# LCD.net
KiCad netlist of a schematic drawn in Altium Designer
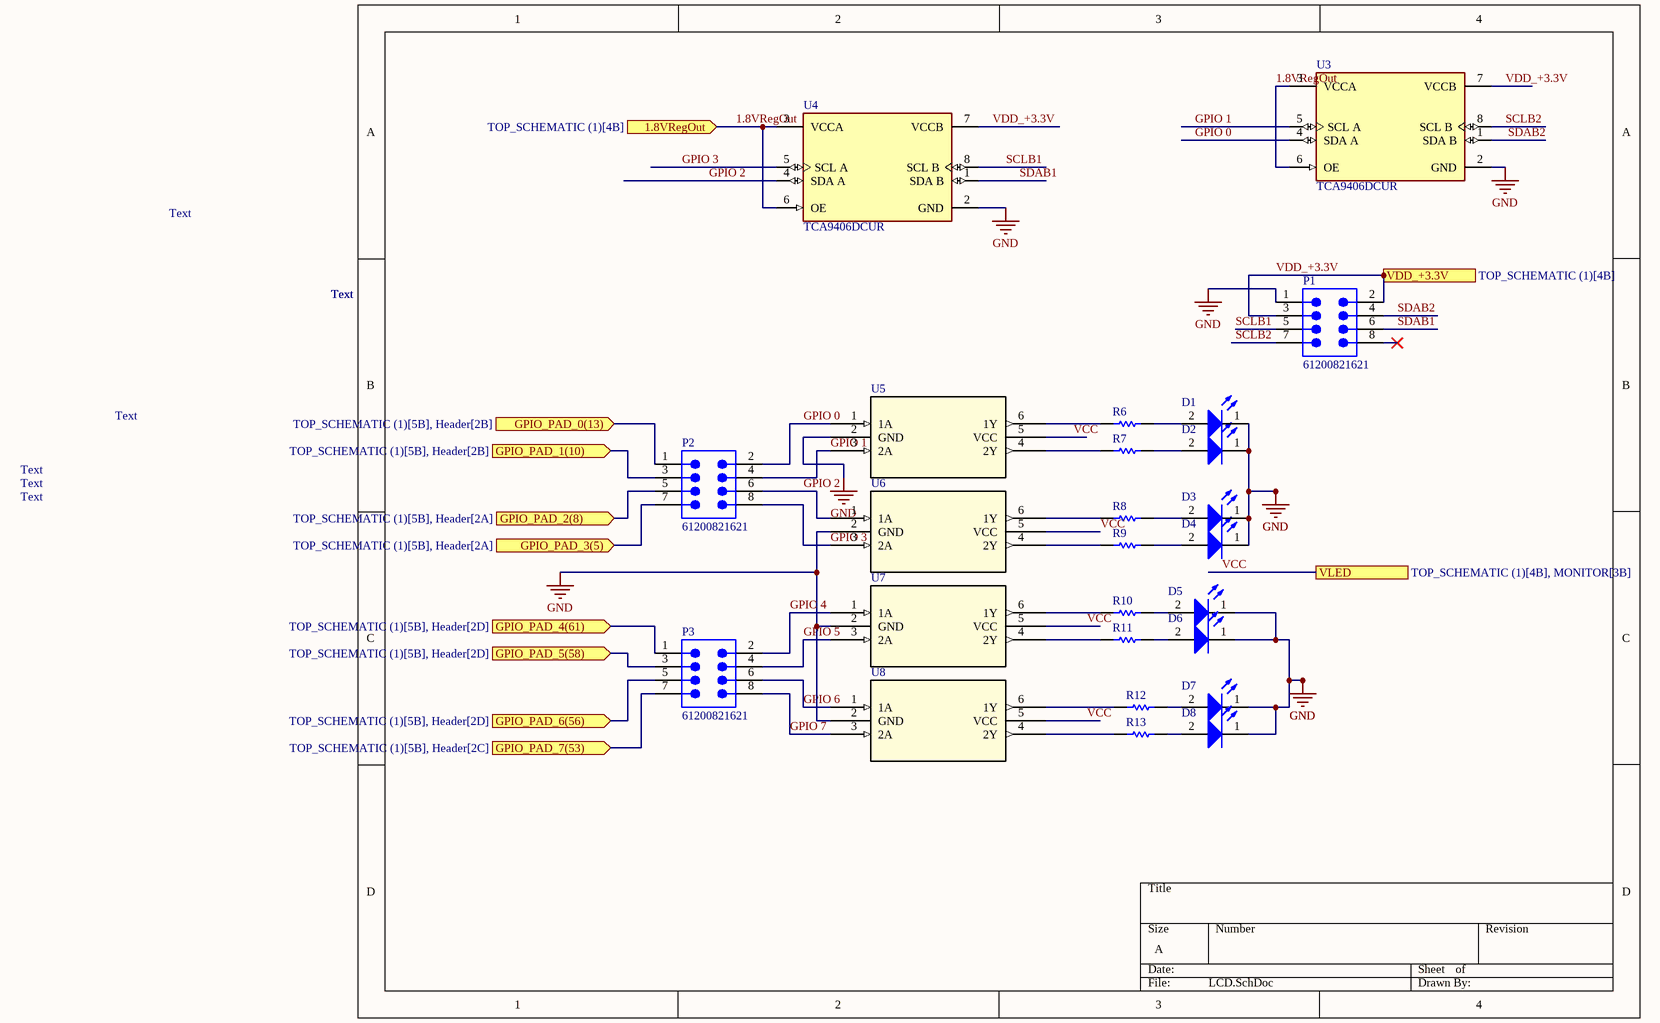
[diagram p0: LCD.SchDoc]

(export (version "E")
  (design (tool "Eeschema 10.0.6"))
  (components
    (comp (ref "D1")
      (value "150120BS75000")
      (footprint "WL-SMCW_1206_150120xx75000")
      (description "Wurth Elektronik LED, WL-SMCW, 3216 (1206), 470 nm, 3.2 x 1.6 x 0.68mm")
      (libsource (lib "Altium Content Vault") (part "LED_Blue_2A-1K"))
    )
    (comp (ref "D2")
      (value "150120BS75000")
      (footprint "WL-SMCW_1206_150120xx75000")
      (description "Wurth Elektronik LED, WL-SMCW, 3216 (1206), 470 nm, 3.2 x 1.6 x 0.68mm")
      (libsource (lib "Altium Content Vault") (part "LED_Blue_2A-1K"))
    )
    (comp (ref "D3")
      (value "150120BS75000")
      (footprint "WL-SMCW_1206_150120xx75000")
      (description "Wurth Elektronik LED, WL-SMCW, 3216 (1206), 470 nm, 3.2 x 1.6 x 0.68mm")
      (libsource (lib "Altium Content Vault") (part "LED_Blue_2A-1K"))
    )
    (comp (ref "D4")
      (value "150120BS75000")
      (footprint "WL-SMCW_1206_150120xx75000")
      (description "Wurth Elektronik LED, WL-SMCW, 3216 (1206), 470 nm, 3.2 x 1.6 x 0.68mm")
      (libsource (lib "Altium Content Vault") (part "LED_Blue_2A-1K"))
    )
    (comp (ref "D5")
      (value "150120BS75000")
      (footprint "WL-SMCW_1206_150120xx75000")
      (description "Wurth Elektronik LED, WL-SMCW, 3216 (1206), 470 nm, 3.2 x 1.6 x 0.68mm")
      (libsource (lib "Altium Content Vault") (part "LED_Blue_2A-1K"))
    )
    (comp (ref "D6")
      (value "150120BS75000")
      (footprint "WL-SMCW_1206_150120xx75000")
      (description "Wurth Elektronik LED, WL-SMCW, 3216 (1206), 470 nm, 3.2 x 1.6 x 0.68mm")
      (libsource (lib "Altium Content Vault") (part "LED_Blue_2A-1K"))
    )
    (comp (ref "D7")
      (value "150120BS75000")
      (footprint "WL-SMCW_1206_150120xx75000")
      (description "Wurth Elektronik LED, WL-SMCW, 3216 (1206), 470 nm, 3.2 x 1.6 x 0.68mm")
      (libsource (lib "Altium Content Vault") (part "LED_Blue_2A-1K"))
    )
    (comp (ref "D8")
      (value "150120BS75000")
      (footprint "WL-SMCW_1206_150120xx75000")
      (description "Wurth Elektronik LED, WL-SMCW, 3216 (1206), 470 nm, 3.2 x 1.6 x 0.68mm")
      (libsource (lib "Altium Content Vault") (part "LED_Blue_2A-1K"))
    )
    (comp (ref "P1")
      (value "61200821621")
      (footprint "61200821621")
      (description "Wr-bhd; 2.54MM Pitch 8 Way 2 Row Shrouded Straight Pcb Header, Surface Mount")
      (libsource (lib "Altium Content Vault") (part "Header_Male_2R_08P"))
    )
    (comp (ref "P2")
      (value "61200821621")
      (footprint "61200821621")
      (description "Wr-bhd; 2.54MM Pitch 8 Way 2 Row Shrouded Straight Pcb Header, Surface Mount")
      (libsource (lib "Altium Content Vault") (part "Header_Male_2R_08P"))
    )
    (comp (ref "P3")
      (value "61200821621")
      (footprint "61200821621")
      (description "Wr-bhd; 2.54MM Pitch 8 Way 2 Row Shrouded Straight Pcb Header, Surface Mount")
      (libsource (lib "Altium Content Vault") (part "Header_Male_2R_08P"))
    )
    (comp (ref "R6")
      (value "RC1206FR-10750RL")
      (footprint "RESC3116X65X40LL10T20")
      (fields (field (name "MANUFACTURER") "Yageo"))
      (libsource (lib "Altium Content Vault") (part "RES"))
    )
    (comp (ref "R7")
      (value "RC1206FR-10750RL")
      (footprint "RESC3116X65X40LL10T20")
      (fields (field (name "MANUFACTURER") "Yageo"))
      (libsource (lib "Altium Content Vault") (part "RES"))
    )
    (comp (ref "R8")
      (value "RC1206FR-10750RL")
      (footprint "RESC3116X65X40LL10T20")
      (fields (field (name "MANUFACTURER") "Yageo"))
      (libsource (lib "Altium Content Vault") (part "RES"))
    )
    (comp (ref "R9")
      (value "RC1206FR-10750RL")
      (footprint "RESC3116X65X40LL10T20")
      (fields (field (name "MANUFACTURER") "Yageo"))
      (libsource (lib "Altium Content Vault") (part "RES"))
    )
    (comp (ref "R10")
      (value "RC1206FR-10750RL")
      (footprint "RESC3116X65X40LL10T20")
      (fields (field (name "MANUFACTURER") "Yageo"))
      (libsource (lib "Altium Content Vault") (part "RES"))
    )
    (comp (ref "R11")
      (value "RC1206FR-10750RL")
      (footprint "RESC3116X65X40LL10T20")
      (fields (field (name "MANUFACTURER") "Yageo"))
      (libsource (lib "Altium Content Vault") (part "RES"))
    )
    (comp (ref "R12")
      (value "RC1206FR-10750RL")
      (footprint "RESC3116X65X40LL10T20")
      (fields (field (name "MANUFACTURER") "Yageo"))
      (libsource (lib "Altium Content Vault") (part "RES"))
    )
    (comp (ref "R13")
      (value "RC1206FR-10750RL")
      (footprint "RESC3116X65X40LL10T20")
      (fields (field (name "MANUFACTURER") "Yageo"))
      (libsource (lib "Altium Content Vault") (part "RES"))
    )
    (comp (ref "U3")
      (value "TCA9406DCUR")
      (footprint "FP-DCU0008A-IPC_B")
      (description "IC TRNSLTR BIDIRECTIONAL US8")
      (libsource (lib "Altium Content Vault") (part "2e2e7ab415e70eec0fdfb76e593e2e7"))
    )
    (comp (ref "U4")
      (value "TCA9406DCUR")
      (footprint "FP-DCU0008A-IPC_B")
      (description "IC TRNSLTR BIDIRECTIONAL US8")
      (libsource (lib "Altium Content Vault") (part "2e2e7ab415e70eec0fdfb76e593e2e7"))
    )
    (comp (ref "U5")
      (value "74LVC2G17GV,125")
      (footprint "SC-74;TSOP6_NEX")
      (description "Description")
      (fields (field (name "COPYRIGHT") "Copyright (C) 2026 Ultra Librarian. All rights reserved."))
      (libsource (lib "74LVC2G17GV,125") (part "74LVC2G17GV,125"))
    )
    (comp (ref "U6")
      (value "74LVC2G17GV,125")
      (footprint "SC-74;TSOP6_NEX")
      (description "Description")
      (fields (field (name "COPYRIGHT") "Copyright (C) 2026 Ultra Librarian. All rights reserved."))
      (libsource (lib "74LVC2G17GV,125") (part "74LVC2G17GV,125"))
    )
    (comp (ref "U7")
      (value "74LVC2G17GV,125")
      (footprint "SC-74;TSOP6_NEX")
      (description "Description")
      (fields (field (name "COPYRIGHT") "Copyright (C) 2026 Ultra Librarian. All rights reserved."))
      (libsource (lib "74LVC2G17GV,125") (part "74LVC2G17GV,125"))
    )
    (comp (ref "U8")
      (value "74LVC2G17GV,125")
      (footprint "SC-74;TSOP6_NEX")
      (description "Description")
      (fields (field (name "COPYRIGHT") "Copyright (C) 2026 Ultra Librarian. All rights reserved."))
      (libsource (lib "74LVC2G17GV,125") (part "74LVC2G17GV,125"))
    )
  )
  (nets
    (net (code "1") (name "/1.8VRegOut") (class "Default")
      (node (ref "U3") (pin "3") (pinfunction "VCCA_3") (pintype "power_in"))
      (node (ref "U3") (pin "6") (pinfunction "OE_6") (pintype "input"))
      (node (ref "U4") (pin "3") (pinfunction "VCCA_3") (pintype "power_in"))
      (node (ref "U4") (pin "6") (pinfunction "OE_6") (pintype "input"))
    )
    (net (code "2") (name "/GPIO 0") (class "Default")
      (node (ref "P2") (pin "2") (pinfunction "2_2") (pintype "passive"))
      (node (ref "U3") (pin "4") (pinfunction "SDA_A_4") (pintype "bidirectional"))
      (node (ref "U5") (pin "1") (pinfunction "1A_1") (pintype "input"))
    )
    (net (code "3") (name "/GPIO 1") (class "Default")
      (node (ref "P2") (pin "4") (pinfunction "4_4") (pintype "passive"))
      (node (ref "U3") (pin "5") (pinfunction "SCL_A_5") (pintype "bidirectional"))
      (node (ref "U5") (pin "3") (pinfunction "2A_3") (pintype "input"))
    )
    (net (code "4") (name "/GPIO 2") (class "Default")
      (node (ref "P2") (pin "6") (pinfunction "6_6") (pintype "passive"))
      (node (ref "U4") (pin "4") (pinfunction "SDA_A_4") (pintype "bidirectional"))
      (node (ref "U6") (pin "1") (pinfunction "1A_1") (pintype "input"))
    )
    (net (code "5") (name "/GPIO 3") (class "Default")
      (node (ref "P2") (pin "8") (pinfunction "8_8") (pintype "passive"))
      (node (ref "U4") (pin "5") (pinfunction "SCL_A_5") (pintype "bidirectional"))
      (node (ref "U6") (pin "3") (pinfunction "2A_3") (pintype "input"))
    )
    (net (code "6") (name "/GPIO 4") (class "Default")
      (node (ref "P3") (pin "2") (pinfunction "2_2") (pintype "passive"))
      (node (ref "U7") (pin "1") (pinfunction "1A_1") (pintype "input"))
    )
    (net (code "7") (name "/GPIO 5") (class "Default")
      (node (ref "P3") (pin "4") (pinfunction "4_4") (pintype "passive"))
      (node (ref "U7") (pin "3") (pinfunction "2A_3") (pintype "input"))
    )
    (net (code "8") (name "/GPIO 6") (class "Default")
      (node (ref "P3") (pin "6") (pinfunction "6_6") (pintype "passive"))
      (node (ref "U8") (pin "1") (pinfunction "1A_1") (pintype "input"))
    )
    (net (code "9") (name "/GPIO 7") (class "Default")
      (node (ref "P3") (pin "8") (pinfunction "8_8") (pintype "passive"))
      (node (ref "U8") (pin "3") (pinfunction "2A_3") (pintype "input"))
    )
    (net (code "10") (name "/GPIO_PAD_0(13)") (class "Default")
      (node (ref "P2") (pin "1") (pinfunction "1_1") (pintype "passive"))
    )
    (net (code "11") (name "/GPIO_PAD_1(10)") (class "Default")
      (node (ref "P2") (pin "3") (pinfunction "3_3") (pintype "passive"))
    )
    (net (code "12") (name "/GPIO_PAD_2(8)") (class "Default")
      (node (ref "P2") (pin "5") (pinfunction "5_5") (pintype "passive"))
    )
    (net (code "13") (name "/GPIO_PAD_3(5)") (class "Default")
      (node (ref "P2") (pin "7") (pinfunction "7_7") (pintype "passive"))
    )
    (net (code "14") (name "/GPIO_PAD_4(61)") (class "Default")
      (node (ref "P3") (pin "1") (pinfunction "1_1") (pintype "passive"))
    )
    (net (code "15") (name "/GPIO_PAD_5(58)") (class "Default")
      (node (ref "P3") (pin "3") (pinfunction "3_3") (pintype "passive"))
    )
    (net (code "16") (name "/GPIO_PAD_6(56)") (class "Default")
      (node (ref "P3") (pin "5") (pinfunction "5_5") (pintype "passive"))
    )
    (net (code "17") (name "/GPIO_PAD_7(53)") (class "Default")
      (node (ref "P3") (pin "7") (pinfunction "7_7") (pintype "passive"))
    )
    (net (code "18") (name "/SCLB1") (class "Default")
      (node (ref "P1") (pin "5") (pinfunction "5_5") (pintype "passive"))
      (node (ref "U4") (pin "8") (pinfunction "SCL_B_8") (pintype "bidirectional"))
    )
    (net (code "19") (name "/SCLB2") (class "Default")
      (node (ref "P1") (pin "7") (pinfunction "7_7") (pintype "passive"))
      (node (ref "U3") (pin "8") (pinfunction "SCL_B_8") (pintype "bidirectional"))
    )
    (net (code "20") (name "/SDAB1") (class "Default")
      (node (ref "P1") (pin "6") (pinfunction "6_6") (pintype "passive"))
      (node (ref "U4") (pin "1") (pinfunction "SDA_B_1") (pintype "bidirectional"))
    )
    (net (code "21") (name "/SDAB2") (class "Default")
      (node (ref "P1") (pin "4") (pinfunction "4_4") (pintype "passive"))
      (node (ref "U3") (pin "1") (pinfunction "SDA_B_1") (pintype "bidirectional"))
    )
    (net (code "22") (name "/VCC") (class "Default")
      (node (ref "U5") (pin "5") (pinfunction "VCC_5") (pintype "power_in"))
      (node (ref "U6") (pin "5") (pinfunction "VCC_5") (pintype "power_in"))
      (node (ref "U7") (pin "5") (pinfunction "VCC_5") (pintype "power_in"))
      (node (ref "U8") (pin "5") (pinfunction "VCC_5") (pintype "power_in"))
    )
    (net (code "23") (name "/VDD_+3.3V") (class "Default")
      (node (ref "P1") (pin "2") (pinfunction "2_2") (pintype "passive"))
      (node (ref "P1") (pin "3") (pinfunction "3_3") (pintype "passive"))
      (node (ref "U3") (pin "7") (pinfunction "VCCB_7") (pintype "power_in"))
      (node (ref "U4") (pin "7") (pinfunction "VCCB_7") (pintype "power_in"))
    )
    (net (code "24") (name "GND") (class "Default")
      (node (ref "D1") (pin "1") (pinfunction "K_1") (pintype "passive"))
      (node (ref "D2") (pin "1") (pinfunction "K_1") (pintype "passive"))
      (node (ref "D3") (pin "1") (pinfunction "K_1") (pintype "passive"))
      (node (ref "D4") (pin "1") (pinfunction "K_1") (pintype "passive"))
      (node (ref "D5") (pin "1") (pinfunction "K_1") (pintype "passive"))
      (node (ref "D6") (pin "1") (pinfunction "K_1") (pintype "passive"))
      (node (ref "D7") (pin "1") (pinfunction "K_1") (pintype "passive"))
      (node (ref "D8") (pin "1") (pinfunction "K_1") (pintype "passive"))
      (node (ref "P1") (pin "1") (pinfunction "1_1") (pintype "passive"))
      (node (ref "U3") (pin "2") (pinfunction "GND_2") (pintype "power_in"))
      (node (ref "U4") (pin "2") (pinfunction "GND_2") (pintype "power_in"))
      (node (ref "U5") (pin "2") (pinfunction "GND_2") (pintype "power_in"))
      (node (ref "U6") (pin "2") (pinfunction "GND_2") (pintype "power_in"))
      (node (ref "U7") (pin "2") (pinfunction "GND_2") (pintype "power_in"))
      (node (ref "U8") (pin "2") (pinfunction "GND_2") (pintype "power_in"))
    )
    (net (code "25") (name "Net-(D1-A)") (class "Default")
      (node (ref "D1") (pin "2") (pinfunction "A_2") (pintype "passive"))
      (node (ref "R6") (pin "2") (pinfunction "2_2") (pintype "passive"))
    )
    (net (code "26") (name "Net-(D2-A)") (class "Default")
      (node (ref "D2") (pin "2") (pinfunction "A_2") (pintype "passive"))
      (node (ref "R7") (pin "2") (pinfunction "2_2") (pintype "passive"))
    )
    (net (code "27") (name "Net-(D3-A)") (class "Default")
      (node (ref "D3") (pin "2") (pinfunction "A_2") (pintype "passive"))
      (node (ref "R8") (pin "2") (pinfunction "2_2") (pintype "passive"))
    )
    (net (code "28") (name "Net-(D4-A)") (class "Default")
      (node (ref "D4") (pin "2") (pinfunction "A_2") (pintype "passive"))
      (node (ref "R9") (pin "2") (pinfunction "2_2") (pintype "passive"))
    )
    (net (code "29") (name "Net-(D5-A)") (class "Default")
      (node (ref "D5") (pin "2") (pinfunction "A_2") (pintype "passive"))
      (node (ref "R10") (pin "2") (pinfunction "2_2") (pintype "passive"))
    )
    (net (code "30") (name "Net-(D6-A)") (class "Default")
      (node (ref "D6") (pin "2") (pinfunction "A_2") (pintype "passive"))
      (node (ref "R11") (pin "2") (pinfunction "2_2") (pintype "passive"))
    )
    (net (code "31") (name "Net-(D7-A)") (class "Default")
      (node (ref "D7") (pin "2") (pinfunction "A_2") (pintype "passive"))
      (node (ref "R12") (pin "2") (pinfunction "2_2") (pintype "passive"))
    )
    (net (code "32") (name "Net-(D8-A)") (class "Default")
      (node (ref "D8") (pin "2") (pinfunction "A_2") (pintype "passive"))
      (node (ref "R13") (pin "2") (pinfunction "2_2") (pintype "passive"))
    )
    (net (code "33") (name "Net-(U5-1Y)") (class "Default")
      (node (ref "R6") (pin "1") (pinfunction "1_1") (pintype "passive"))
      (node (ref "U5") (pin "6") (pinfunction "1Y_6") (pintype "output"))
    )
    (net (code "34") (name "Net-(U5-2Y)") (class "Default")
      (node (ref "R7") (pin "1") (pinfunction "1_1") (pintype "passive"))
      (node (ref "U5") (pin "4") (pinfunction "2Y_4") (pintype "output"))
    )
    (net (code "35") (name "Net-(U6-1Y)") (class "Default")
      (node (ref "R8") (pin "1") (pinfunction "1_1") (pintype "passive"))
      (node (ref "U6") (pin "6") (pinfunction "1Y_6") (pintype "output"))
    )
    (net (code "36") (name "Net-(U6-2Y)") (class "Default")
      (node (ref "R9") (pin "1") (pinfunction "1_1") (pintype "passive"))
      (node (ref "U6") (pin "4") (pinfunction "2Y_4") (pintype "output"))
    )
    (net (code "37") (name "Net-(U7-1Y)") (class "Default")
      (node (ref "R10") (pin "1") (pinfunction "1_1") (pintype "passive"))
      (node (ref "U7") (pin "6") (pinfunction "1Y_6") (pintype "output"))
    )
    (net (code "38") (name "Net-(U7-2Y)") (class "Default")
      (node (ref "R11") (pin "1") (pinfunction "1_1") (pintype "passive"))
      (node (ref "U7") (pin "4") (pinfunction "2Y_4") (pintype "output"))
    )
    (net (code "39") (name "Net-(U8-1Y)") (class "Default")
      (node (ref "R12") (pin "1") (pinfunction "1_1") (pintype "passive"))
      (node (ref "U8") (pin "6") (pinfunction "1Y_6") (pintype "output"))
    )
    (net (code "40") (name "Net-(U8-2Y)") (class "Default")
      (node (ref "R13") (pin "1") (pinfunction "1_1") (pintype "passive"))
      (node (ref "U8") (pin "4") (pinfunction "2Y_4") (pintype "output"))
    )
    (net (code "41") (name "unconnected-(P1-Pad8)") (class "Default")
      (node (ref "P1") (pin "8") (pinfunction "8_8") (pintype "passive+no_connect"))
    )
  )
)
